# SCH_0321_2023-05-09.net
KiCad netlist of a schematic drawn in EasyEDA
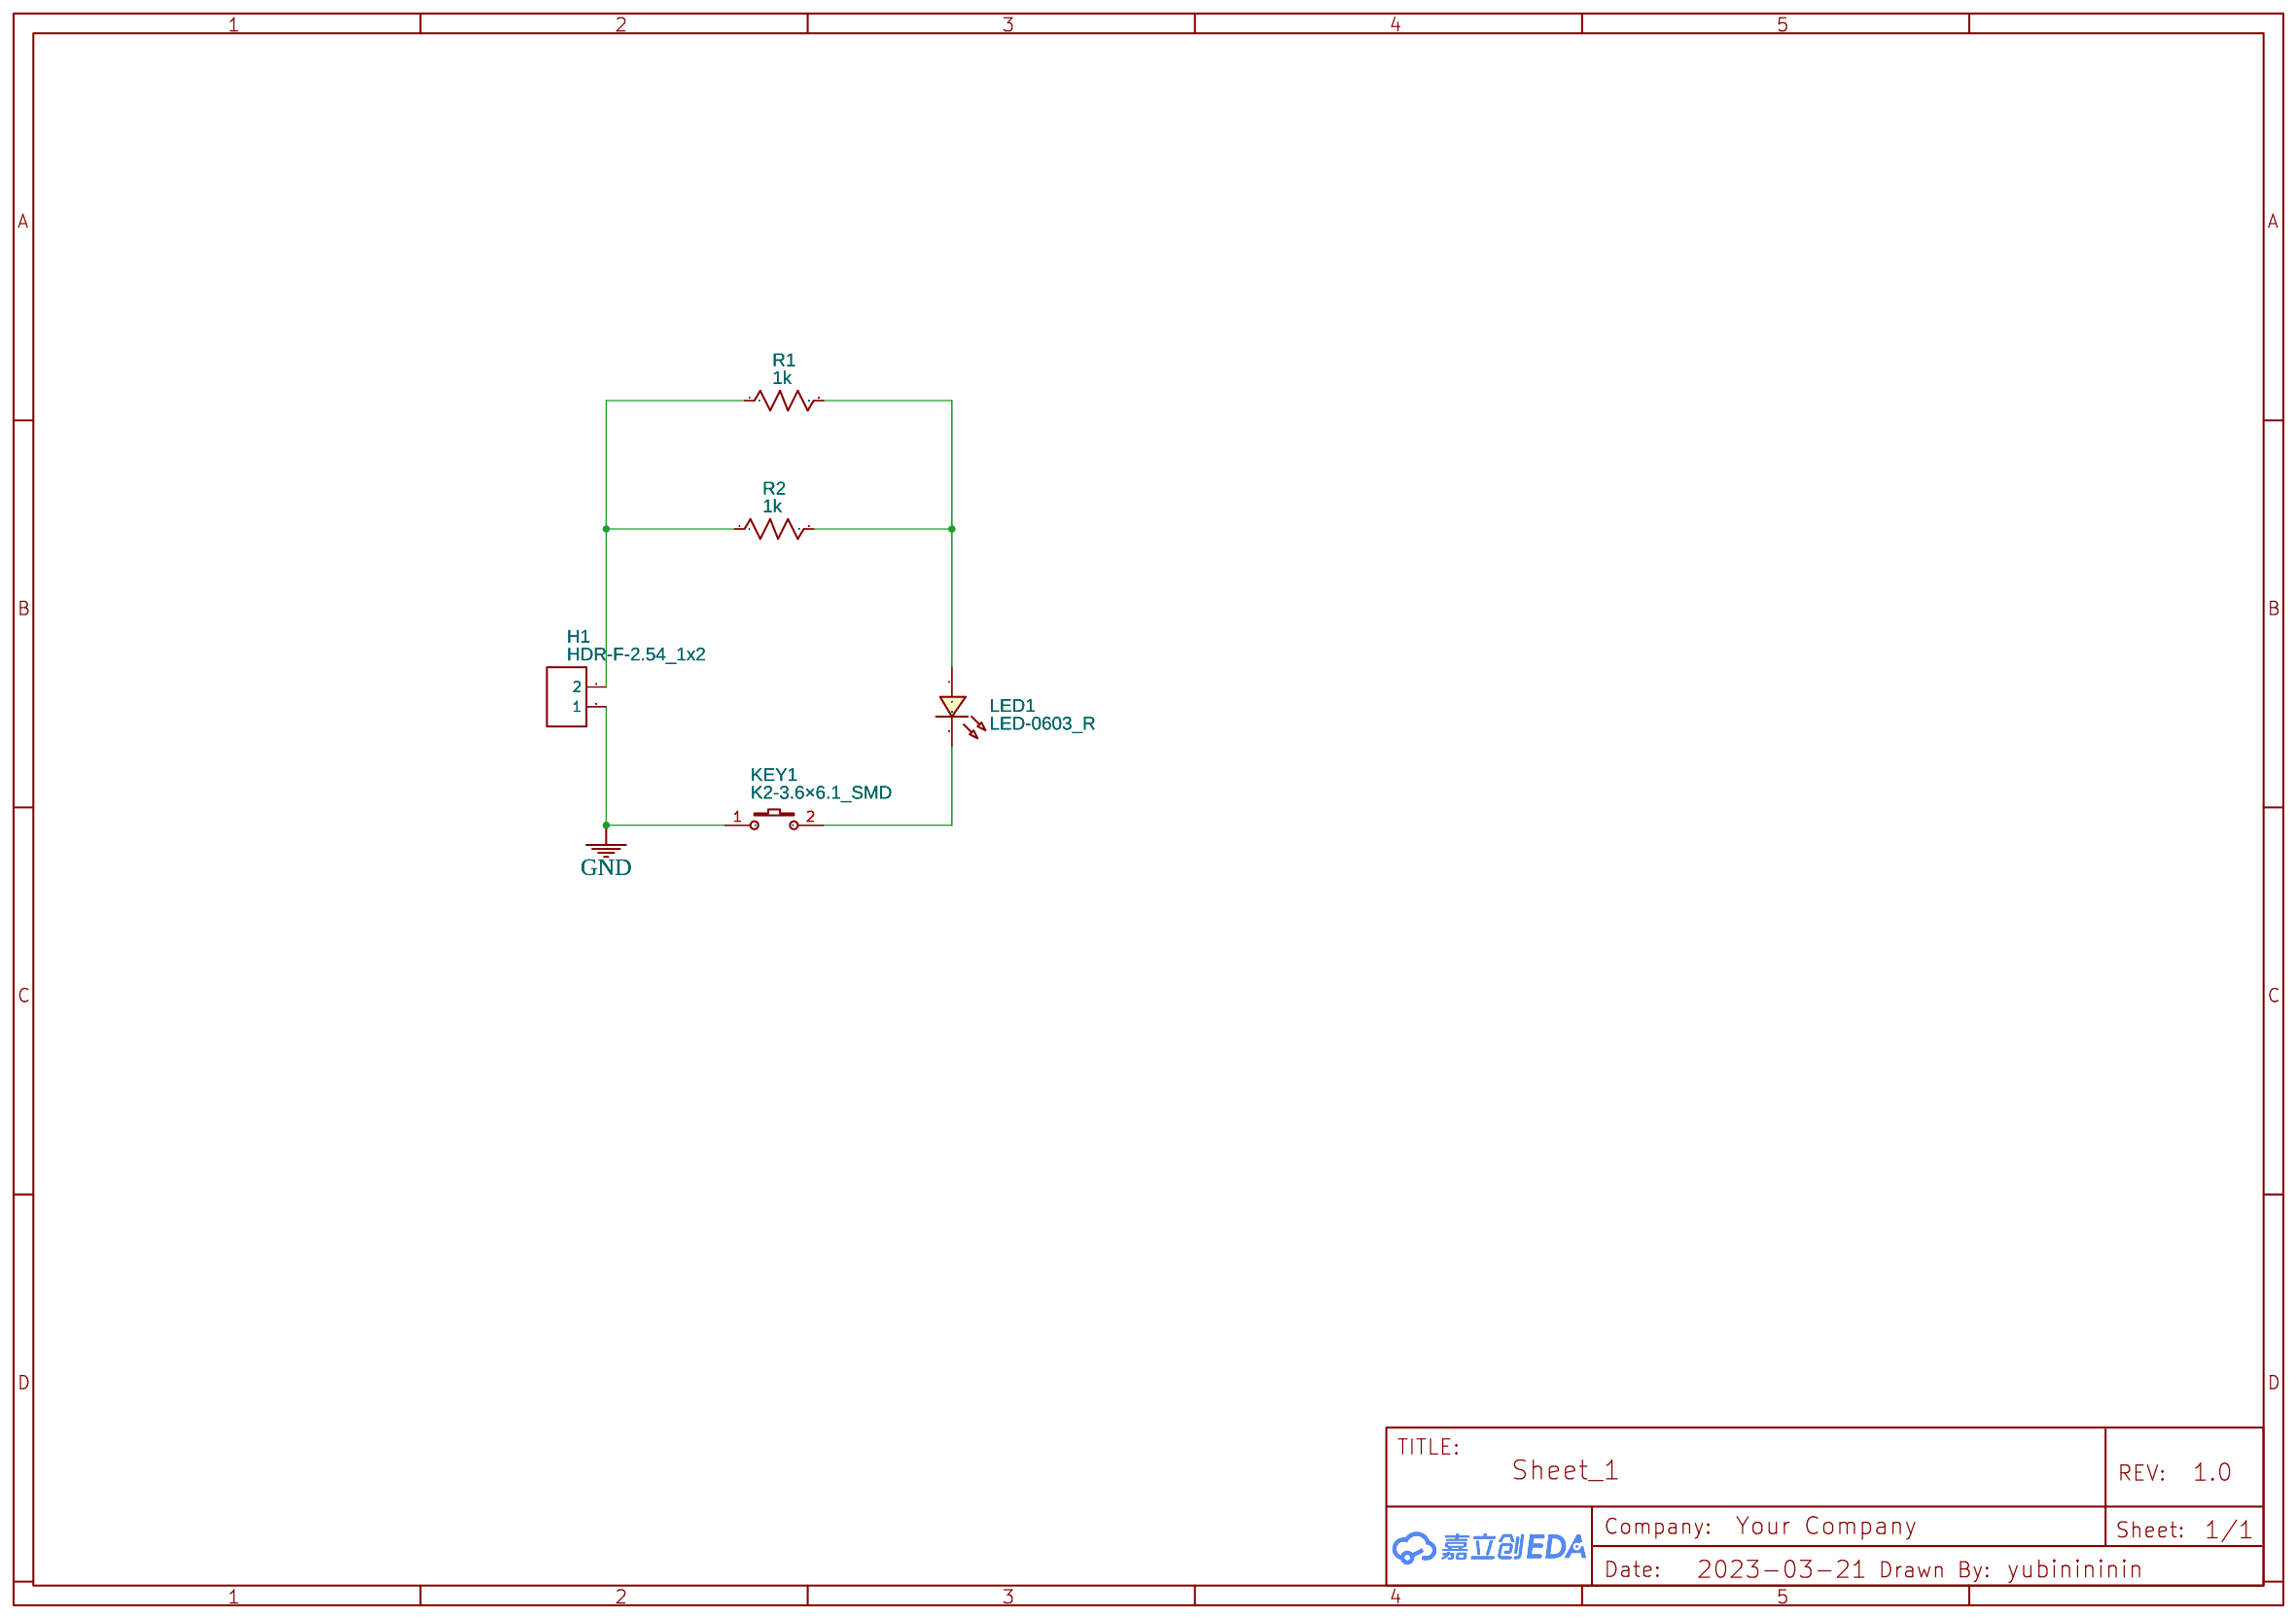
[diagram p0: schematic sheet]

(export (version "E")
  (design (tool "Eeschema 10.0.6"))
  (components
    (comp (ref "H1")
      (value "HDR-F-2.54_1x2")
      (fields (field (name "BOM_Supplier Part") "C49661"))
      (libsource (lib "") (part "HDR-F-2.54_1x2"))
    )
    (comp (ref "KEY1")
      (value "K2-3.6×6.1_SMD")
      (fields
        (field (name "BOM_Manufacturer Part") "K2-1107ST-A4SW-06")
        (field (name "BOM_Supplier Part") "C118141")
      )
      (libsource (lib "") (part "K2-3.6×6.1_SMD"))
    )
    (comp (ref "LED1")
      (value "LED-0603_R")
      (fields
        (field (name "BOM_Manufacturer Part") "19-217/R6C-AL1M2VY/3T")
        (field (name "BOM_Supplier Part") "C72044")
      )
      (libsource (lib "") (part "LED-0603_R"))
    )
    (comp (ref "R1") (value "1k") (libsource (lib "") (part "R_0603_US")))
    (comp (ref "R2") (value "1k") (libsource (lib "") (part "R_0603_US")))
  )
  (nets
    (net (code "1") (name "GND") (class "Default")
      (node (ref "H1") (pin "1") (pinfunction "1_1") (pintype "input"))
      (node (ref "KEY1") (pin "1") (pinfunction "1_1") (pintype "unspecified"))
    )
    (net (code "2") (name "Net-(H1-Pad2)") (class "Default")
      (node (ref "H1") (pin "2") (pinfunction "2_2") (pintype "input"))
      (node (ref "R1") (pin "1") (pinfunction "1_1") (pintype "unspecified"))
      (node (ref "R2") (pin "1") (pinfunction "1_1") (pintype "unspecified"))
    )
    (net (code "3") (name "Net-(KEY1-Pad2)") (class "Default")
      (node (ref "KEY1") (pin "2") (pinfunction "2_2") (pintype "unspecified"))
      (node (ref "LED1") (pin "2") (pinfunction "2_2") (pintype "unspecified"))
    )
    (net (code "4") (name "Net-(LED1-Pad1)") (class "Default")
      (node (ref "LED1") (pin "1") (pinfunction "1_1") (pintype "unspecified"))
      (node (ref "R1") (pin "2") (pinfunction "2_2") (pintype "unspecified"))
      (node (ref "R2") (pin "2") (pinfunction "2_2") (pintype "unspecified"))
    )
  )
)
